# DSO_Front.net
KiCad netlist of a schematic drawn in Altium Designer
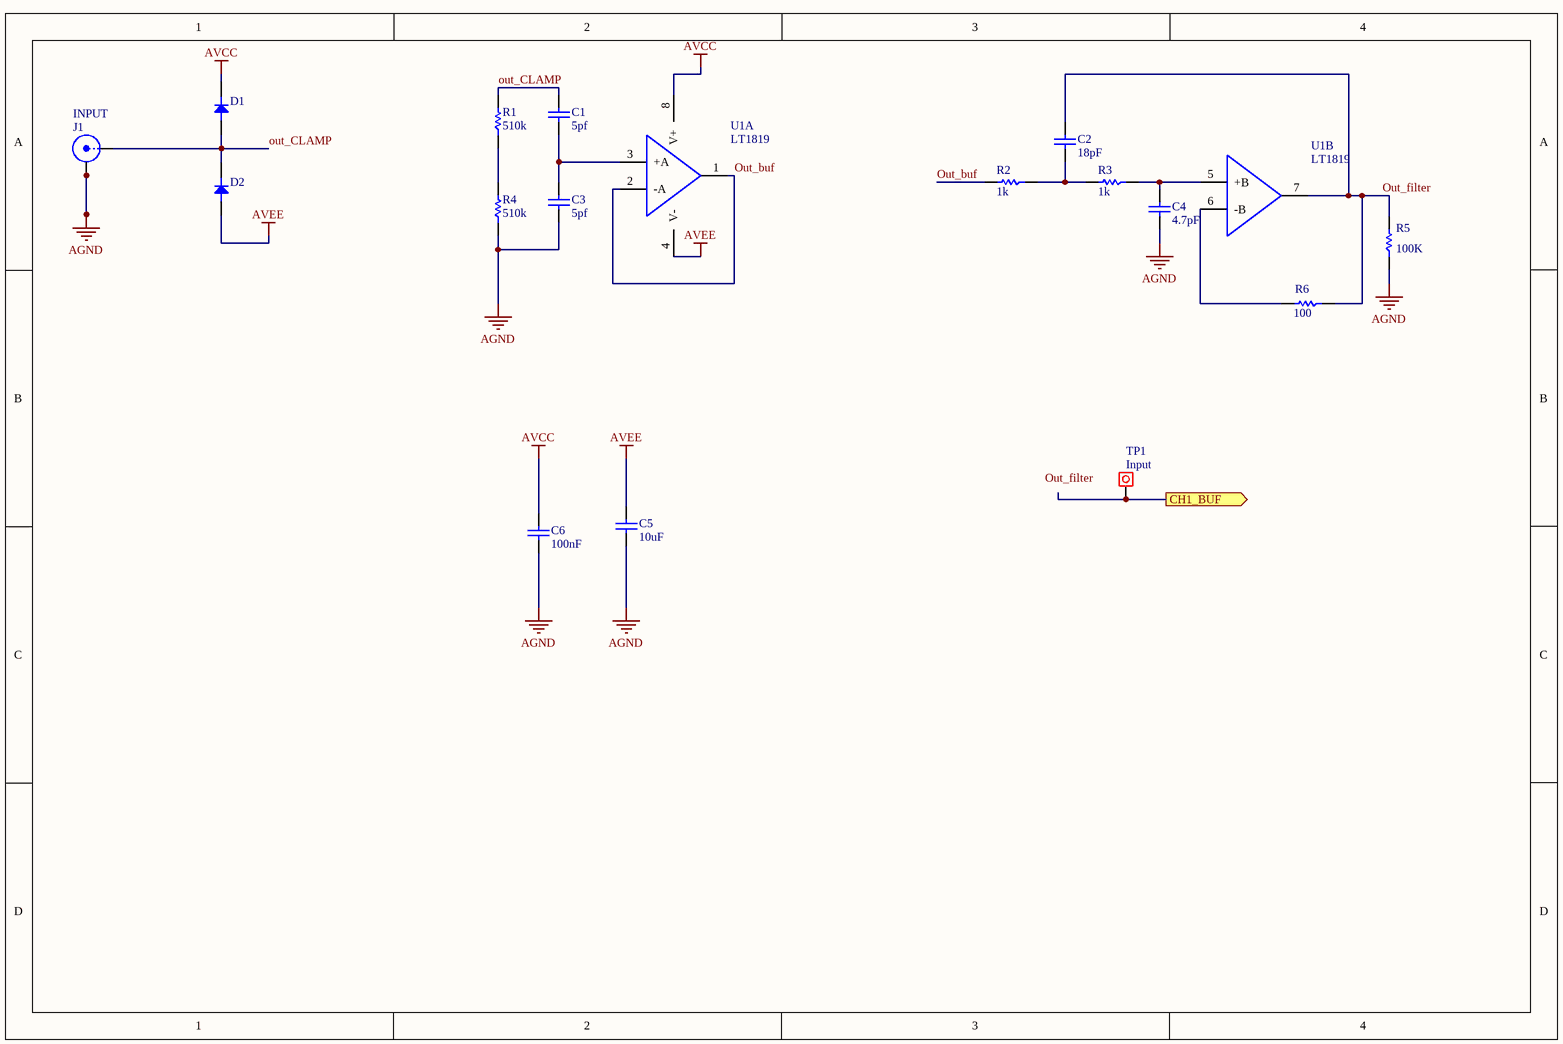
[diagram p0: DSO_Front.SchDoc]

(export (version "E")
  (design (tool "Eeschema 10.0.6"))
  (components
    (comp (ref "C1")
      (value "5pf")
      (footprint "0805C")
      (description "Capacitor")
      (fields (field (name "REVIEWED BY") "RM - 2018/08/05"))
      (libsource (lib "DSO") (part "C"))
    )
    (comp (ref "C2")
      (value "18pF")
      (footprint "0805C")
      (description "Capacitor")
      (fields (field (name "REVIEWED BY") "RM - 2018/08/05"))
      (libsource (lib "DSO") (part "C"))
    )
    (comp (ref "C3")
      (value "5pf")
      (footprint "0805C")
      (description "Capacitor")
      (fields (field (name "REVIEWED BY") "RM - 2018/08/05"))
      (libsource (lib "DSO") (part "C"))
    )
    (comp (ref "C4")
      (value "4.7pF")
      (footprint "0805C")
      (description "Capacitor")
      (fields (field (name "REVIEWED BY") "RM - 2018/08/05"))
      (libsource (lib "DSO") (part "C"))
    )
    (comp (ref "C5")
      (value "10uF")
      (footprint "0805C")
      (description "Capacitor")
      (fields (field (name "REVIEWED BY") "RM - 2018/08/05"))
      (libsource (lib "DSO") (part "C"))
    )
    (comp (ref "C6")
      (value "100nF")
      (footprint "0805C")
      (description "Capacitor")
      (fields (field (name "REVIEWED BY") "RM - 2018/08/05"))
      (libsource (lib "DSO") (part "C"))
    )
    (comp (ref "D1")
      (value "Diode")
      (footprint "SOD-123")
      (fields (field (name "REVIEWED BY") "RM - 2018/08/05"))
      (libsource (lib "DSO") (part "D"))
    )
    (comp (ref "D2")
      (value "Diode")
      (footprint "SOD-123")
      (fields (field (name "REVIEWED BY") "RM - 2018/08/05"))
      (libsource (lib "DSO") (part "D"))
    )
    (comp (ref "J1")
      (value "INPUT")
      (footprint "BNC_VERT")
      (description "BNC Straight")
      (fields (field (name "REVIEWED BY") "RM - 2018/08/05"))
      (libsource (lib "DSO") (part "BNC"))
    )
    (comp (ref "R1")
      (value "510k")
      (footprint "0805")
      (description "Resistor")
      (fields (field (name "REVIEWED BY") "RM - 2018/08/05"))
      (libsource (lib "DSO") (part "R"))
    )
    (comp (ref "R2")
      (value "1k")
      (footprint "0805")
      (description "Resistor")
      (fields (field (name "REVIEWED BY") "RM - 2018/08/05"))
      (libsource (lib "DSO") (part "R"))
    )
    (comp (ref "R3")
      (value "1k")
      (footprint "0805")
      (description "Resistor")
      (fields (field (name "REVIEWED BY") "RM - 2018/08/05"))
      (libsource (lib "DSO") (part "R"))
    )
    (comp (ref "R4")
      (value "510k")
      (footprint "0805")
      (description "Resistor")
      (fields (field (name "REVIEWED BY") "RM - 2018/08/05"))
      (libsource (lib "DSO") (part "R"))
    )
    (comp (ref "R5")
      (value "100K")
      (footprint "0805")
      (description "Resistor")
      (fields (field (name "REVIEWED BY") "RM - 2018/08/05"))
      (libsource (lib "DSO") (part "R"))
    )
    (comp (ref "R6")
      (value "100")
      (footprint "0805")
      (description "Resistor")
      (fields (field (name "REVIEWED BY") "RM - 2018/08/05"))
      (libsource (lib "DSO") (part "R"))
    )
    (comp (ref "TP1")
      (value "Input")
      (footprint "Testpoin")
      (description "Pad")
      (fields (field (name "Comment") "INPUT"))
      (libsource (lib "DSO") (part "Test Point"))
    )
    (comp (ref "U1")
      (value "LT1819")
      (footprint "MSOP-8")
      (description "OpAmp High Frequency Dual")
      (fields (field (name "REVIEWED BY") "RM - 2018/08/05"))
      (libsource (lib "DSO") (part "LT1819"))
    )
  )
  (nets
    (net (code "1") (name "/CH1_BUF") (class "Default") (node (ref "TP1") (pin "1") (pintype "passive")))
    (net (code "2") (name "/Out_buf") (class "Default")
      (node (ref "R2") (pin "2") (pintype "passive"))
      (node (ref "U1") (pin "1") (pinfunction "OUTA_1") (pintype "passive"))
      (node (ref "U1") (pin "2") (pinfunction "-A_2") (pintype "passive"))
    )
    (net (code "3") (name "/Out_filter") (class "Default")
      (node (ref "C2") (pin "1") (pinfunction "1_1") (pintype "passive"))
      (node (ref "R5") (pin "2") (pintype "passive"))
      (node (ref "R6") (pin "1") (pintype "passive"))
      (node (ref "U1") (pin "7") (pinfunction "OUTB_7") (pintype "passive"))
    )
    (net (code "4") (name "/out_CLAMP") (class "Default")
      (node (ref "C1") (pin "1") (pinfunction "1_1") (pintype "passive"))
      (node (ref "D1") (pin "A") (pinfunction "A_A") (pintype "passive"))
      (node (ref "D2") (pin "K") (pinfunction "K_K") (pintype "passive"))
      (node (ref "J1") (pin "1") (pinfunction "X_1") (pintype "passive"))
      (node (ref "R1") (pin "2") (pintype "passive"))
    )
    (net (code "5") (name "AGND") (class "Default")
      (node (ref "C3") (pin "2") (pinfunction "2_2") (pintype "passive"))
      (node (ref "C4") (pin "2") (pinfunction "2_2") (pintype "passive"))
      (node (ref "C5") (pin "2") (pinfunction "2_2") (pintype "passive"))
      (node (ref "C6") (pin "2") (pinfunction "2_2") (pintype "passive"))
      (node (ref "J1") (pin "2") (pinfunction "Y_2") (pintype "passive"))
      (node (ref "J1") (pin "3") (pinfunction "Y_3") (pintype "passive"))
      (node (ref "J1") (pin "4") (pinfunction "Y_4") (pintype "passive"))
      (node (ref "J1") (pin "5") (pinfunction "Y_5") (pintype "passive"))
      (node (ref "R4") (pin "1") (pintype "passive"))
      (node (ref "R5") (pin "1") (pintype "passive"))
    )
    (net (code "6") (name "AVCC") (class "Default")
      (node (ref "C6") (pin "1") (pinfunction "1_1") (pintype "passive"))
      (node (ref "D1") (pin "K") (pinfunction "K_K") (pintype "passive"))
      (node (ref "U1") (pin "8") (pinfunction "V+_8") (pintype "passive"))
    )
    (net (code "7") (name "AVEE") (class "Default")
      (node (ref "C5") (pin "1") (pinfunction "1_1") (pintype "passive"))
      (node (ref "D2") (pin "A") (pinfunction "A_A") (pintype "passive"))
      (node (ref "U1") (pin "4") (pinfunction "V-_4") (pintype "passive"))
    )
    (net (code "8") (name "Net-(C2-Pad2)") (class "Default")
      (node (ref "C2") (pin "2") (pinfunction "2_2") (pintype "passive"))
      (node (ref "R2") (pin "1") (pintype "passive"))
      (node (ref "R3") (pin "2") (pintype "passive"))
    )
    (net (code "9") (name "Net-(R1-Pad1)") (class "Default")
      (node (ref "R1") (pin "1") (pintype "passive"))
      (node (ref "R4") (pin "2") (pintype "passive"))
    )
    (net (code "10") (name "Net-(U1A-+A)") (class "Default")
      (node (ref "C1") (pin "2") (pinfunction "2_2") (pintype "passive"))
      (node (ref "C3") (pin "1") (pinfunction "1_1") (pintype "passive"))
      (node (ref "U1") (pin "3") (pinfunction "+A_3") (pintype "passive"))
    )
    (net (code "11") (name "Net-(U1B-+B)") (class "Default")
      (node (ref "C4") (pin "1") (pinfunction "1_1") (pintype "passive"))
      (node (ref "R3") (pin "1") (pintype "passive"))
      (node (ref "U1") (pin "5") (pinfunction "+B_5") (pintype "passive"))
    )
    (net (code "12") (name "Net-(U1B--B)") (class "Default")
      (node (ref "R6") (pin "2") (pintype "passive"))
      (node (ref "U1") (pin "6") (pinfunction "-B_6") (pintype "passive"))
    )
  )
)
